# DriveIGBT2020.net
KiCad netlist of a schematic drawn in Altium Designer
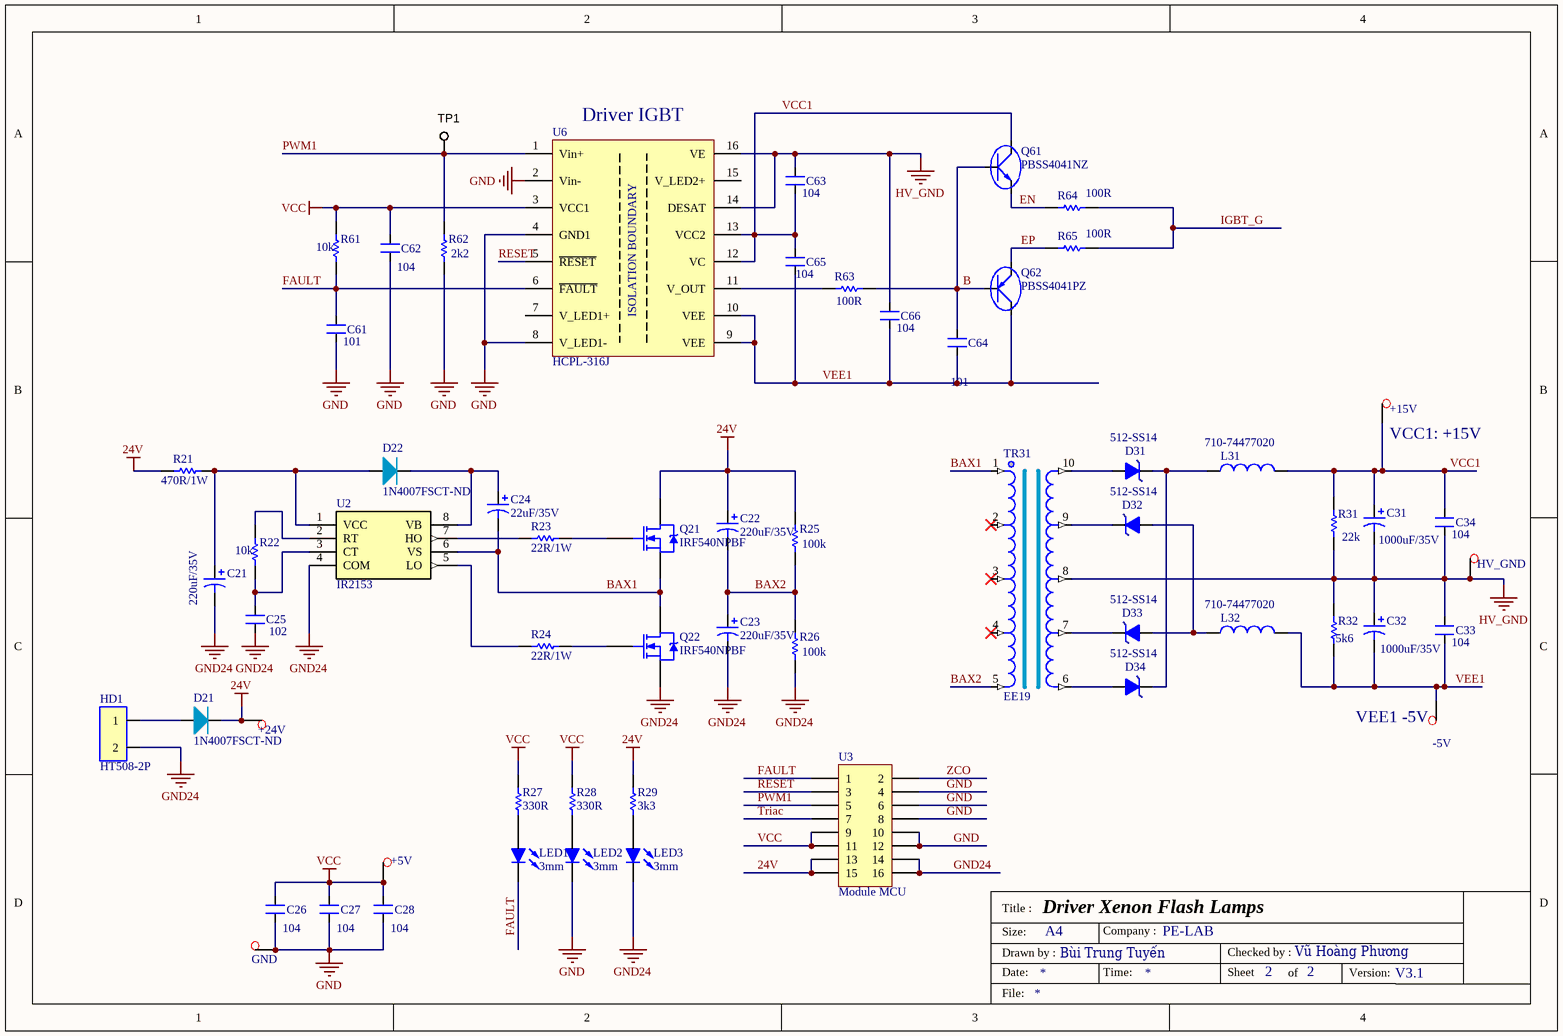
[diagram p0: DriveIGBT2020.SchDoc]

(export (version "E")
  (design (tool "Eeschema 10.0.6"))
  (components
    (comp (ref "+5V") (value "TP") (footprint "swatpcblib:TP2") (libsource (lib "swatpcblib") (part "TP")))
    (comp (ref "+15V") (value "TP") (footprint "swatpcblib:TP2") (libsource (lib "swatpcblib") (part "TP")))
    (comp (ref "+24V") (value "TP") (footprint "swatpcblib:TP2") (libsource (lib "swatpcblib") (part "TP")))
    (comp (ref "-5V") (value "TP") (footprint "swatpcblib:TP2") (libsource (lib "swatpcblib") (part "TP")))
    (comp (ref "C21")
      (value "220uF/35V")
      (footprint "CP1.5/3.4")
      (description "Tụ hóa 220uF/35V cắm")
      (libsource (lib "Schematic Library") (part "CP"))
    )
    (comp (ref "C22")
      (value "220uF/35V")
      (footprint "CP1.5/3.4")
      (description "Tụ hóa 220uF/35V cắm")
      (libsource (lib "Schematic Library") (part "CP"))
    )
    (comp (ref "C23")
      (value "220uF/35V")
      (footprint "CP1.5/3.4")
      (description "Tụ hóa 220uF/35V cắm")
      (libsource (lib "Schematic Library") (part "CP"))
    )
    (comp (ref "C24")
      (value "22uF/35V")
      (footprint "CP1.5/3.4")
      (description "Tụ hóa 100uF/35V cắm")
      (libsource (lib "Schematic Library") (part "CP"))
    )
    (comp (ref "C25")
      (value "102")
      (footprint "CAPC3216N")
      (description "Tụ dán SMD 1206")
      (fields (field (name "Comment") "Tụ dán SMD 1206102"))
      (libsource (lib "Schematic Library") (part "CN"))
    )
    (comp (ref "C26")
      (value "104")
      (footprint "CAPC3216N")
      (description "Tụ dán SMD 1206")
      (fields (field (name "Comment") "Tụ dán SMD 1206104"))
      (libsource (lib "Schematic Library") (part "CN"))
    )
    (comp (ref "C27")
      (value "104")
      (footprint "CAPC3216N")
      (description "Tụ dán SMD 1206")
      (fields (field (name "Comment") "Tụ dán SMD 1206104"))
      (libsource (lib "Schematic Library") (part "CN"))
    )
    (comp (ref "C28")
      (value "104")
      (footprint "CAPC3216N")
      (description "Tụ dán SMD 1206")
      (fields (field (name "Comment") "Tụ dán SMD 1206104"))
      (libsource (lib "Schematic Library") (part "CN"))
    )
    (comp (ref "C31")
      (value "1000uF/35V")
      (footprint "CP1.5/3.4")
      (description "Tụ hóa 1000uF/35V cắm")
      (libsource (lib "Schematic Library") (part "CP"))
    )
    (comp (ref "C32")
      (value "1000uF/35V")
      (footprint "CP1.5/3.4")
      (description "Tụ hóa 1000uF/35V cắm")
      (libsource (lib "Schematic Library") (part "CP"))
    )
    (comp (ref "C33")
      (value "104")
      (footprint "CAPC3216N")
      (description "Tụ dán SMD 1206")
      (fields (field (name "Comment") "Tụ dán SMD 1206104"))
      (libsource (lib "Schematic Library") (part "CN"))
    )
    (comp (ref "C34")
      (value "104")
      (footprint "CAPC3216N")
      (description "Tụ dán SMD 1206")
      (fields (field (name "Comment") "Tụ dán SMD 1206104"))
      (libsource (lib "Schematic Library") (part "CN"))
    )
    (comp (ref "C61")
      (value "101")
      (footprint "CAPC3216N")
      (description "Tụ dán SMD 1206")
      (fields (field (name "Comment") "Tụ dán SMD 1206101"))
      (libsource (lib "Schematic Library") (part "CN"))
    )
    (comp (ref "C62")
      (value "104")
      (footprint "CAPC3216N")
      (description "Tụ dán SMD 1206")
      (fields (field (name "Comment") "Tụ dán SMD 1206104"))
      (libsource (lib "Schematic Library") (part "CN"))
    )
    (comp (ref "C63")
      (value "104")
      (footprint "CAPC3216N")
      (description "Tụ dán SMD 1206")
      (fields (field (name "Comment") "Tụ dán SMD 1206104"))
      (libsource (lib "Schematic Library") (part "CN"))
    )
    (comp (ref "C64")
      (value "101")
      (footprint "CAPC3216N")
      (description "Tụ dán SMD 1206")
      (fields (field (name "Comment") "Tụ dán SMD 1206101"))
      (libsource (lib "Schematic Library") (part "CN"))
    )
    (comp (ref "C65")
      (value "104")
      (footprint "CAPC3216N")
      (description "Tụ dán SMD 1206")
      (fields (field (name "Comment") "Tụ dán SMD 1206104"))
      (libsource (lib "Schematic Library") (part "CN"))
    )
    (comp (ref "C66")
      (value "104")
      (footprint "CAPC3216N")
      (description "Tụ dán SMD 1206")
      (fields (field (name "Comment") "Tụ dán SMD 1206104"))
      (libsource (lib "Schematic Library") (part "CN"))
    )
    (comp (ref "D21")
      (value "Đi ốt cắm1N4007FSCT-ND")
      (footprint "swatpcblib:DO-41")
      (fields
        (field (name "VL1") "1N4007FSCT-ND")
        (field (name "MANUFACTURER") "ON Semiconductor / Fairchild")
        (field (name "MANUFACTURER PART NUMBER") "1N4007")
      )
      (libsource (lib "swatpcblib") (part "Diode"))
    )
    (comp (ref "D22")
      (value "Đi ốt cắm1N4007FSCT-ND")
      (footprint "swatpcblib:DO-41")
      (fields
        (field (name "VL1") "1N4007FSCT-ND")
        (field (name "MANUFACTURER") "ON Semiconductor / Fairchild")
        (field (name "MANUFACTURER PART NUMBER") "1N4007")
      )
      (libsource (lib "swatpcblib") (part "Diode"))
    )
    (comp (ref "D31")
      (value "Diode nhanh dán512-SS14")
      (footprint "DO-214AC")
      (description "Diode nhanh dán")
      (fields
        (field (name "VL1") "512-SS14")
        (field (name "MANUFACTURER") "ON Semiconductor / Fairchild")
        (field (name "MANUFACTURER PART NUMBER") "SS14")
      )
      (libsource (lib "Schematic Library") (part "Diode"))
    )
    (comp (ref "D32")
      (value "Diode nhanh dán512-SS14")
      (footprint "DO-214AC")
      (description "Diode nhanh dán")
      (fields
        (field (name "VL1") "512-SS14")
        (field (name "MANUFACTURER") "ON Semiconductor / Fairchild")
        (field (name "MANUFACTURER PART NUMBER") "SS14")
      )
      (libsource (lib "Schematic Library") (part "Diode"))
    )
    (comp (ref "D33")
      (value "Diode nhanh dán512-SS14")
      (footprint "DO-214AC")
      (description "Diode nhanh dán")
      (fields
        (field (name "VL1") "512-SS14")
        (field (name "MANUFACTURER") "ON Semiconductor / Fairchild")
        (field (name "MANUFACTURER PART NUMBER") "SS14")
      )
      (libsource (lib "Schematic Library") (part "Diode"))
    )
    (comp (ref "D34")
      (value "Diode nhanh dán512-SS14")
      (footprint "DO-214AC")
      (description "Diode nhanh dán")
      (fields
        (field (name "VL1") "512-SS14")
        (field (name "MANUFACTURER") "ON Semiconductor / Fairchild")
        (field (name "MANUFACTURER PART NUMBER") "SS14")
      )
      (libsource (lib "Schematic Library") (part "Diode"))
    )
    (comp (ref "GND") (value "TP") (footprint "swatpcblib:TP2") (libsource (lib "swatpcblib") (part "TP")))
    (comp (ref "HD1")
      (value "HT508-2P")
      (footprint "HT508-2P")
      (description "300V 10A")
      (libsource (lib "Schematic Library") (part "HEADER2"))
    )
    (comp (ref "HV_GND") (value "TP") (footprint "swatpcblib:TP2") (libsource (lib "swatpcblib") (part "TP")))
    (comp (ref "L31")
      (value "Cuộn cảm dán SMD100uH74477020")
      (footprint "L-SMD-M-12x10")
      (description "Cuộn cảm dán SMD")
      (fields
        (field (name "SUPPLIER PART NUMBER 1") "710-74477020")
        (field (name "MANUFACTURER") "Wurth Electronics")
        (field (name "TOLERANCE") "20%")
      )
      (libsource (lib "Schematic Library") (part "Inductor"))
    )
    (comp (ref "L32")
      (value "Cuộn cảm dán SMD100uH74477020")
      (footprint "L-SMD-M-12x10")
      (description "Cuộn cảm dán SMD")
      (fields
        (field (name "SUPPLIER PART NUMBER 1") "710-74477020")
        (field (name "MANUFACTURER") "Wurth Electronics")
        (field (name "TOLERANCE") "20%")
      )
      (libsource (lib "Schematic Library") (part "Inductor"))
    )
    (comp (ref "LED1")
      (value "3mm")
      (footprint "LED 3mm")
      (description "Led đỏ chân cắm")
      (libsource (lib "Schematic Library") (part "LED 3mm"))
    )
    (comp (ref "LED2")
      (value "3mm")
      (footprint "LED 3mm")
      (description "Led xanh chân cắm")
      (libsource (lib "Schematic Library") (part "LED 3mm"))
    )
    (comp (ref "LED3")
      (value "3mm")
      (footprint "LED 3mm")
      (description "Led xanh chân cắm")
      (libsource (lib "Schematic Library") (part "LED 3mm"))
    )
    (comp (ref "Q21")
      (value "IRF540NPBF")
      (footprint "TO-220-HEATSINK")
      (description "HEXFET Power MOSFET")
      (fields (field (name "MANUFACTURER") "International Rectifier"))
      (libsource (lib "Schematic Library") (part "IRF540N"))
    )
    (comp (ref "Q22")
      (value "IRF540NPBF")
      (footprint "TO-220-HEATSINK")
      (description "HEXFET Power MOSFET")
      (fields (field (name "MANUFACTURER") "International Rectifier"))
      (libsource (lib "Schematic Library") (part "IRF540N"))
    )
    (comp (ref "Q61")
      (value "PBSS4041NZ")
      (footprint "SOT223")
      (description "TRANS NPN 60V 7A SOT223")
      (fields
        (field (name "MANUFACTURER") "NXP Semiconductors")
        (field (name "MANUFACTURER PART NUMBER") "PBSS4041NZ,115")
      )
      (libsource (lib "Schematic Library") (part "PBSS4041NZ"))
    )
    (comp (ref "Q62")
      (value "PBSS4041PZ")
      (footprint "SOT223")
      (description "TRANS PNP 60V 5.7A SOT223")
      (fields
        (field (name "MANUFACTURER") "NXP Semiconductors")
        (field (name "MANUFACTURER PART NUMBER") "PBSS4041PZ,115")
      )
      (libsource (lib "Schematic Library") (part "PBSS4041PZ"))
    )
    (comp (ref "R21")
      (value "470R/1W")
      (footprint "RES-1W")
      (description "Trở cắm 1W")
      (libsource (lib "Schematic Library") (part "Resistor"))
    )
    (comp (ref "R22")
      (value "10k")
      (footprint "RES-SMD-1206")
      (description "Trở dán SMD 1206")
      (fields (field (name "Comment") "Trở dán SMD 120610k"))
      (libsource (lib "Schematic Library") (part "Resistor"))
    )
    (comp (ref "R23")
      (value "22R/1W")
      (footprint "RES-1W")
      (description "Trở cắm 1W")
      (libsource (lib "Schematic Library") (part "Resistor"))
    )
    (comp (ref "R24")
      (value "22R/1W")
      (footprint "RES-1W")
      (description "Trở cắm 1W")
      (libsource (lib "Schematic Library") (part "Resistor"))
    )
    (comp (ref "R25")
      (value "100k")
      (footprint "RES-SMD-1206")
      (description "Trở dán SMD 1206")
      (fields (field (name "Comment") "Trở dán SMD 1206100k"))
      (libsource (lib "Schematic Library") (part "Resistor"))
    )
    (comp (ref "R26")
      (value "100k")
      (footprint "RES-SMD-1206")
      (description "Trở dán SMD 1206")
      (fields (field (name "Comment") "Trở dán SMD 1206100k"))
      (libsource (lib "Schematic Library") (part "Resistor"))
    )
    (comp (ref "R27")
      (value "330R")
      (footprint "RES-SMD-1206")
      (description "Trở dán SMD 1206")
      (libsource (lib "Schematic Library") (part "Resistor"))
    )
    (comp (ref "R28")
      (value "330R")
      (footprint "RES-SMD-1206")
      (description "Trở dán SMD 1206")
      (libsource (lib "Schematic Library") (part "Resistor"))
    )
    (comp (ref "R29")
      (value "3k3")
      (footprint "RES-SMD-1206")
      (description "Trở dán SMD 1206")
      (libsource (lib "Schematic Library") (part "Resistor"))
    )
    (comp (ref "R31")
      (value "22k")
      (footprint "RES-SMD-1206")
      (description "Trở dán SMD 1206")
      (fields (field (name "Comment") "Trở dán SMD 120622k"))
      (libsource (lib "Schematic Library") (part "Resistor"))
    )
    (comp (ref "R32")
      (value "5k6")
      (footprint "RES-SMD-1206")
      (description "Trở dán SMD 1206")
      (fields (field (name "Comment") "Trở dán SMD 12065k6"))
      (libsource (lib "Schematic Library") (part "Resistor"))
    )
    (comp (ref "R61")
      (value "10k")
      (footprint "RES-SMD-1206")
      (description "Trở dán SMD 1206")
      (fields (field (name "Comment") "Trở dán SMD 120610k"))
      (libsource (lib "Schematic Library") (part "Resistor"))
    )
    (comp (ref "R62")
      (value "2k2")
      (footprint "RES-SMD-1206")
      (description "Trở dán SMD 1206")
      (fields (field (name "Comment") "Trở dán SMD 12062k2"))
      (libsource (lib "Schematic Library") (part "Resistor"))
    )
    (comp (ref "R63")
      (value "100R")
      (footprint "RES-SMD-1206")
      (description "Trở dán SMD 1206")
      (fields (field (name "Comment") "Trở dán SMD 1206100R"))
      (libsource (lib "Schematic Library") (part "Resistor"))
    )
    (comp (ref "R64")
      (value "100R")
      (footprint "RES-1W")
      (description "Trở cắm 1W")
      (fields (field (name "Comment") "Trở cắm 1W100R"))
      (libsource (lib "Schematic Library") (part "Resistor"))
    )
    (comp (ref "R65")
      (value "100R")
      (footprint "RES-1W")
      (description "Trở cắm 1W")
      (fields (field (name "Comment") "Trở cắm 1W100R"))
      (libsource (lib "Schematic Library") (part "Resistor"))
    )
    (comp (ref "TP1")
      (value "TESTPOINT_LEAD")
      (footprint "TP")
      (description "TEST POINT")
      (libsource (lib "PBL - Test Points") (part "TESTPOINT_LEAD"))
    )
    (comp (ref "TR31")
      (value "EE19")
      (footprint "EE19")
      (libsource (lib "Schematic Library") (part "Tranformer"))
    )
    (comp (ref "U2")
      (value "IR2153")
      (footprint "DIP8/W0.3")
      (description "IC, MOSFET/IGBT DRIVER HALF BRIDGE")
      (fields
        (field (name "MANUFACTURER") "International Rectifier")
        (field (name "MANUFACTURER PART NUMBER") "IR2153PBF")
      )
      (libsource (lib "Schematic Library") (part "IR2153"))
    )
    (comp (ref "U3")
      (value "Module MCU")
      (footprint "MCU CONTROL")
      (libsource (lib "Schematic Library") (part "Module MCU"))
    )
    (comp (ref "U6")
      (value "HCPL-316J")
      (footprint "SO16")
      (description "BROADCOM LIMITED         HCPL-316J-500E             OPTOCOUPLER, GATE DRIVE, 1-CH, 3.75KV")
      (fields
        (field (name "MANUFACTURER") "Broadcom")
        (field (name "MANUFACTURER PART NUMBER") "HCPL-316J-500E")
      )
      (libsource (lib "Schematic Library") (part "HCPL-316J"))
    )
  )
  (nets
    (net (code "1") (name "/B") (class "Default")
      (node (ref "C64") (pin "2") (pinfunction "2_2") (pintype "passive"))
      (node (ref "Q61") (pin "1") (pinfunction "B_1") (pintype "passive"))
      (node (ref "Q62") (pin "1") (pinfunction "B_1") (pintype "passive"))
      (node (ref "R63") (pin "1") (pinfunction "1_1") (pintype "passive"))
    )
    (net (code "2") (name "/BAX1") (class "Default")
      (node (ref "C24") (pin "2") (pinfunction "2_2") (pintype "passive"))
      (node (ref "Q21") (pin "3") (pinfunction "S_3") (pintype "passive"))
      (node (ref "Q22") (pin "2") (pinfunction "D_2") (pintype "passive"))
      (node (ref "TR31") (pin "1") (pinfunction "1_1") (pintype "input"))
      (node (ref "U2") (pin "6") (pinfunction "VS_6") (pintype "power_in"))
    )
    (net (code "3") (name "/BAX2") (class "Default")
      (node (ref "C22") (pin "2") (pinfunction "2_2") (pintype "passive"))
      (node (ref "C23") (pin "1") (pinfunction "1_1") (pintype "passive"))
      (node (ref "R25") (pin "1") (pinfunction "1_1") (pintype "passive"))
      (node (ref "R26") (pin "2") (pinfunction "2_2") (pintype "passive"))
      (node (ref "TR31") (pin "5") (pinfunction "5_5") (pintype "input"))
    )
    (net (code "4") (name "/EN") (class "Default")
      (node (ref "Q61") (pin "3") (pinfunction "E_3") (pintype "passive"))
      (node (ref "R64") (pin "2") (pinfunction "2_2") (pintype "passive"))
    )
    (net (code "5") (name "/EP") (class "Default")
      (node (ref "Q62") (pin "3") (pinfunction "E_3") (pintype "passive"))
      (node (ref "R65") (pin "2") (pinfunction "2_2") (pintype "passive"))
    )
    (net (code "6") (name "/FAULT") (class "Default")
      (node (ref "C61") (pin "2") (pinfunction "2_2") (pintype "passive"))
      (node (ref "LED1") (pin "2") (pinfunction "2_2") (pintype "passive"))
      (node (ref "R61") (pin "1") (pinfunction "1_1") (pintype "passive"))
      (node (ref "U3") (pin "1") (pinfunction "1_1") (pintype "passive"))
      (node (ref "U6") (pin "6") (pinfunction "~{FAULT}_6") (pintype "passive"))
    )
    (net (code "7") (name "/IGBT_G") (class "Default")
      (node (ref "R64") (pin "1") (pinfunction "1_1") (pintype "passive"))
      (node (ref "R65") (pin "1") (pinfunction "1_1") (pintype "passive"))
    )
    (net (code "8") (name "/PWM1") (class "Default")
      (node (ref "R62") (pin "2") (pinfunction "2_2") (pintype "passive"))
      (node (ref "TP1") (pin "1") (pintype "passive"))
      (node (ref "U3") (pin "5") (pinfunction "5_5") (pintype "passive"))
      (node (ref "U6") (pin "1") (pinfunction "Vin+_1") (pintype "passive"))
    )
    (net (code "9") (name "/RESET") (class "Default")
      (node (ref "U3") (pin "3") (pinfunction "3_3") (pintype "passive"))
      (node (ref "U6") (pin "5") (pinfunction "~{RESET}_5") (pintype "passive"))
    )
    (net (code "10") (name "/Triac") (class "Default")
      (node (ref "U3") (pin "7") (pinfunction "7_7") (pintype "passive"))
    )
    (net (code "11") (name "/VCC1") (class "Default")
      (node (ref "+15V") (pin "1") (pinfunction "1_1") (pintype "passive"))
      (node (ref "C31") (pin "1") (pinfunction "1_1") (pintype "passive"))
      (node (ref "C34") (pin "2") (pinfunction "2_2") (pintype "passive"))
      (node (ref "C63") (pin "1") (pinfunction "1_1") (pintype "passive"))
      (node (ref "C65") (pin "2") (pinfunction "2_2") (pintype "passive"))
      (node (ref "L31") (pin "2") (pinfunction "2_2") (pintype "passive"))
      (node (ref "Q61") (pin "2") (pinfunction "C_2") (pintype "passive"))
      (node (ref "R31") (pin "1") (pinfunction "1_1") (pintype "passive"))
      (node (ref "U6") (pin "12") (pinfunction "VC_12") (pintype "passive"))
      (node (ref "U6") (pin "13") (pinfunction "VCC2_13") (pintype "passive"))
    )
    (net (code "12") (name "/VEE1") (class "Default")
      (node (ref "-5V") (pin "1") (pinfunction "1_1") (pintype "passive"))
      (node (ref "C32") (pin "2") (pinfunction "2_2") (pintype "passive"))
      (node (ref "C33") (pin "1") (pinfunction "1_1") (pintype "passive"))
      (node (ref "C64") (pin "1") (pinfunction "1_1") (pintype "passive"))
      (node (ref "C65") (pin "1") (pinfunction "1_1") (pintype "passive"))
      (node (ref "C66") (pin "1") (pinfunction "1_1") (pintype "passive"))
      (node (ref "L32") (pin "2") (pinfunction "2_2") (pintype "passive"))
      (node (ref "Q62") (pin "2") (pinfunction "C_2") (pintype "passive"))
      (node (ref "R32") (pin "2") (pinfunction "2_2") (pintype "passive"))
      (node (ref "U6") (pin "10") (pinfunction "VEE_10") (pintype "passive"))
      (node (ref "U6") (pin "9") (pinfunction "VEE_9") (pintype "passive"))
    )
    (net (code "13") (name "/ZCO") (class "Default")
      (node (ref "U3") (pin "2") (pinfunction "2_2") (pintype "passive"))
    )
    (net (code "14") (name "24V") (class "Default")
      (node (ref "+24V") (pin "1") (pinfunction "1_1") (pintype "passive"))
      (node (ref "C22") (pin "1") (pinfunction "1_1") (pintype "passive"))
      (node (ref "D21") (pin "K") (pinfunction "K_K") (pintype "passive"))
      (node (ref "Q21") (pin "2") (pinfunction "D_2") (pintype "passive"))
      (node (ref "R21") (pin "1") (pinfunction "1_1") (pintype "passive"))
      (node (ref "R25") (pin "2") (pinfunction "2_2") (pintype "passive"))
      (node (ref "R29") (pin "1") (pinfunction "1_1") (pintype "passive"))
      (node (ref "U3") (pin "13") (pinfunction "13_13") (pintype "passive"))
      (node (ref "U3") (pin "15") (pinfunction "15_15") (pintype "passive"))
    )
    (net (code "15") (name "GND") (class "Default")
      (node (ref "C26") (pin "1") (pinfunction "1_1") (pintype "passive"))
      (node (ref "C27") (pin "1") (pinfunction "1_1") (pintype "passive"))
      (node (ref "C28") (pin "1") (pinfunction "1_1") (pintype "passive"))
      (node (ref "C61") (pin "1") (pinfunction "1_1") (pintype "passive"))
      (node (ref "C62") (pin "1") (pinfunction "1_1") (pintype "passive"))
      (node (ref "GND") (pin "1") (pinfunction "1_1") (pintype "passive"))
      (node (ref "LED2") (pin "2") (pinfunction "2_2") (pintype "passive"))
      (node (ref "R62") (pin "1") (pinfunction "1_1") (pintype "passive"))
      (node (ref "U3") (pin "10") (pinfunction "10_10") (pintype "passive"))
      (node (ref "U3") (pin "12") (pinfunction "12_12") (pintype "passive"))
      (node (ref "U3") (pin "4") (pinfunction "4_4") (pintype "passive"))
      (node (ref "U3") (pin "6") (pinfunction "6_6") (pintype "passive"))
      (node (ref "U3") (pin "8") (pinfunction "8_8") (pintype "passive"))
      (node (ref "U6") (pin "2") (pinfunction "Vin-_2") (pintype "passive"))
      (node (ref "U6") (pin "4") (pinfunction "GND1_4") (pintype "passive"))
      (node (ref "U6") (pin "8") (pinfunction "V_LED1-_8") (pintype "passive"))
    )
    (net (code "16") (name "GND24") (class "Default")
      (node (ref "C21") (pin "2") (pinfunction "2_2") (pintype "passive"))
      (node (ref "C23") (pin "2") (pinfunction "2_2") (pintype "passive"))
      (node (ref "C25") (pin "1") (pinfunction "1_1") (pintype "passive"))
      (node (ref "HD1") (pin "2") (pinfunction "2_2") (pintype "passive"))
      (node (ref "LED3") (pin "2") (pinfunction "2_2") (pintype "passive"))
      (node (ref "Q22") (pin "3") (pinfunction "S_3") (pintype "passive"))
      (node (ref "R26") (pin "1") (pinfunction "1_1") (pintype "passive"))
      (node (ref "U2") (pin "4") (pinfunction "COM_4") (pintype "power_in"))
      (node (ref "U3") (pin "14") (pinfunction "14_14") (pintype "passive"))
      (node (ref "U3") (pin "16") (pinfunction "16_16") (pintype "passive"))
    )
    (net (code "17") (name "HV_GND") (class "Default")
      (node (ref "C31") (pin "2") (pinfunction "2_2") (pintype "passive"))
      (node (ref "C32") (pin "1") (pinfunction "1_1") (pintype "passive"))
      (node (ref "C33") (pin "2") (pinfunction "2_2") (pintype "passive"))
      (node (ref "C34") (pin "1") (pinfunction "1_1") (pintype "passive"))
      (node (ref "C63") (pin "2") (pinfunction "2_2") (pintype "passive"))
      (node (ref "C66") (pin "2") (pinfunction "2_2") (pintype "passive"))
      (node (ref "HV_GND") (pin "1") (pinfunction "1_1") (pintype "passive"))
      (node (ref "R31") (pin "2") (pinfunction "2_2") (pintype "passive"))
      (node (ref "R32") (pin "1") (pinfunction "1_1") (pintype "passive"))
      (node (ref "TR31") (pin "8") (pinfunction "8_8") (pintype "output"))
      (node (ref "U6") (pin "14") (pinfunction "DESAT_14") (pintype "passive"))
      (node (ref "U6") (pin "16") (pinfunction "VE_16") (pintype "passive"))
    )
    (net (code "18") (name "Net-(D21-PadA)") (class "Default")
      (node (ref "D21") (pin "A") (pinfunction "A_A") (pintype "passive"))
      (node (ref "HD1") (pin "1") (pinfunction "1_1") (pintype "passive"))
    )
    (net (code "19") (name "Net-(D31-A)") (class "Default")
      (node (ref "D31") (pin "1") (pinfunction "A_1") (pintype "passive"))
      (node (ref "TR31") (pin "10") (pinfunction "10_10") (pintype "output"))
    )
    (net (code "20") (name "Net-(D31-K)") (class "Default")
      (node (ref "D31") (pin "2") (pinfunction "K_2") (pintype "passive"))
      (node (ref "D34") (pin "2") (pinfunction "K_2") (pintype "passive"))
      (node (ref "L31") (pin "1") (pinfunction "1_1") (pintype "passive"))
    )
    (net (code "21") (name "Net-(D32-A)") (class "Default")
      (node (ref "D32") (pin "1") (pinfunction "A_1") (pintype "passive"))
      (node (ref "D33") (pin "1") (pinfunction "A_1") (pintype "passive"))
      (node (ref "L32") (pin "1") (pinfunction "1_1") (pintype "passive"))
    )
    (net (code "22") (name "Net-(D32-K)") (class "Default")
      (node (ref "D32") (pin "2") (pinfunction "K_2") (pintype "passive"))
      (node (ref "TR31") (pin "9") (pinfunction "9_9") (pintype "output"))
    )
    (net (code "23") (name "Net-(D33-K)") (class "Default")
      (node (ref "D33") (pin "2") (pinfunction "K_2") (pintype "passive"))
      (node (ref "TR31") (pin "7") (pinfunction "7_7") (pintype "output"))
    )
    (net (code "24") (name "Net-(D34-A)") (class "Default")
      (node (ref "D34") (pin "1") (pinfunction "A_1") (pintype "passive"))
      (node (ref "TR31") (pin "6") (pinfunction "6_6") (pintype "output"))
    )
    (net (code "25") (name "Net-(LED1-Pad1)") (class "Default")
      (node (ref "LED1") (pin "1") (pinfunction "1_1") (pintype "passive"))
      (node (ref "R27") (pin "2") (pinfunction "2_2") (pintype "passive"))
    )
    (net (code "26") (name "Net-(LED2-Pad1)") (class "Default")
      (node (ref "LED2") (pin "1") (pinfunction "1_1") (pintype "passive"))
      (node (ref "R28") (pin "2") (pinfunction "2_2") (pintype "passive"))
    )
    (net (code "27") (name "Net-(LED3-Pad1)") (class "Default")
      (node (ref "LED3") (pin "1") (pinfunction "1_1") (pintype "passive"))
      (node (ref "R29") (pin "2") (pinfunction "2_2") (pintype "passive"))
    )
    (net (code "28") (name "Net-(Q21-G)") (class "Default")
      (node (ref "Q21") (pin "1") (pinfunction "G_1") (pintype "passive"))
      (node (ref "R23") (pin "1") (pinfunction "1_1") (pintype "passive"))
    )
    (net (code "29") (name "Net-(Q22-G)") (class "Default")
      (node (ref "Q22") (pin "1") (pinfunction "G_1") (pintype "passive"))
      (node (ref "R24") (pin "1") (pinfunction "1_1") (pintype "passive"))
    )
    (net (code "30") (name "Net-(U2-CT)") (class "Default")
      (node (ref "C25") (pin "2") (pinfunction "2_2") (pintype "passive"))
      (node (ref "R22") (pin "1") (pinfunction "1_1") (pintype "passive"))
      (node (ref "U2") (pin "3") (pinfunction "CT_3") (pintype "passive"))
    )
    (net (code "31") (name "Net-(U2-HO)") (class "Default")
      (node (ref "R23") (pin "2") (pinfunction "2_2") (pintype "passive"))
      (node (ref "U2") (pin "7") (pinfunction "HO_7") (pintype "output"))
    )
    (net (code "32") (name "Net-(U2-LO)") (class "Default")
      (node (ref "R24") (pin "2") (pinfunction "2_2") (pintype "passive"))
      (node (ref "U2") (pin "5") (pinfunction "LO_5") (pintype "output"))
    )
    (net (code "33") (name "Net-(U2-RT)") (class "Default")
      (node (ref "R22") (pin "2") (pinfunction "2_2") (pintype "passive"))
      (node (ref "U2") (pin "2") (pinfunction "RT_2") (pintype "passive"))
    )
    (net (code "34") (name "Net-(U2-VB)") (class "Default")
      (node (ref "C24") (pin "1") (pinfunction "1_1") (pintype "passive"))
      (node (ref "D22") (pin "K") (pinfunction "K_K") (pintype "passive"))
      (node (ref "U2") (pin "8") (pinfunction "VB_8") (pintype "power_in"))
    )
    (net (code "35") (name "Net-(U2-VCC)") (class "Default")
      (node (ref "C21") (pin "1") (pinfunction "1_1") (pintype "passive"))
      (node (ref "D22") (pin "A") (pinfunction "A_A") (pintype "passive"))
      (node (ref "R21") (pin "2") (pinfunction "2_2") (pintype "passive"))
      (node (ref "U2") (pin "1") (pinfunction "VCC_1") (pintype "power_in"))
    )
    (net (code "36") (name "Net-(U6-V_OUT)") (class "Default")
      (node (ref "R63") (pin "2") (pinfunction "2_2") (pintype "passive"))
      (node (ref "U6") (pin "11") (pinfunction "V_OUT_11") (pintype "passive"))
    )
    (net (code "37") (name "VCC") (class "Default")
      (node (ref "+5V") (pin "1") (pinfunction "1_1") (pintype "passive"))
      (node (ref "C26") (pin "2") (pinfunction "2_2") (pintype "passive"))
      (node (ref "C27") (pin "2") (pinfunction "2_2") (pintype "passive"))
      (node (ref "C28") (pin "2") (pinfunction "2_2") (pintype "passive"))
      (node (ref "C62") (pin "2") (pinfunction "2_2") (pintype "passive"))
      (node (ref "R27") (pin "1") (pinfunction "1_1") (pintype "passive"))
      (node (ref "R28") (pin "1") (pinfunction "1_1") (pintype "passive"))
      (node (ref "R61") (pin "2") (pinfunction "2_2") (pintype "passive"))
      (node (ref "U3") (pin "11") (pinfunction "11_11") (pintype "passive"))
      (node (ref "U3") (pin "9") (pinfunction "9_9") (pintype "passive"))
      (node (ref "U6") (pin "3") (pinfunction "VCC1_3") (pintype "passive"))
    )
    (net (code "38") (name "unconnected-(TR31-Pad2)") (class "Default")
      (node (ref "TR31") (pin "2") (pinfunction "2_2") (pintype "input+no_connect"))
    )
    (net (code "39") (name "unconnected-(TR31-Pad3)") (class "Default")
      (node (ref "TR31") (pin "3") (pinfunction "3_3") (pintype "input+no_connect"))
    )
    (net (code "40") (name "unconnected-(TR31-Pad4)") (class "Default")
      (node (ref "TR31") (pin "4") (pinfunction "4_4") (pintype "input+no_connect"))
    )
    (net (code "41") (name "unconnected-(U6-V_LED1+-Pad7)") (class "Default")
      (node (ref "U6") (pin "7") (pinfunction "V_LED1+_7") (pintype "passive"))
    )
    (net (code "42") (name "unconnected-(U6-V_LED2+-Pad15)") (class "Default")
      (node (ref "U6") (pin "15") (pinfunction "V_LED2+_15") (pintype "passive"))
    )
  )
)
